# Train_Barrier.net
KiCad netlist of a schematic drawn in EasyEDA
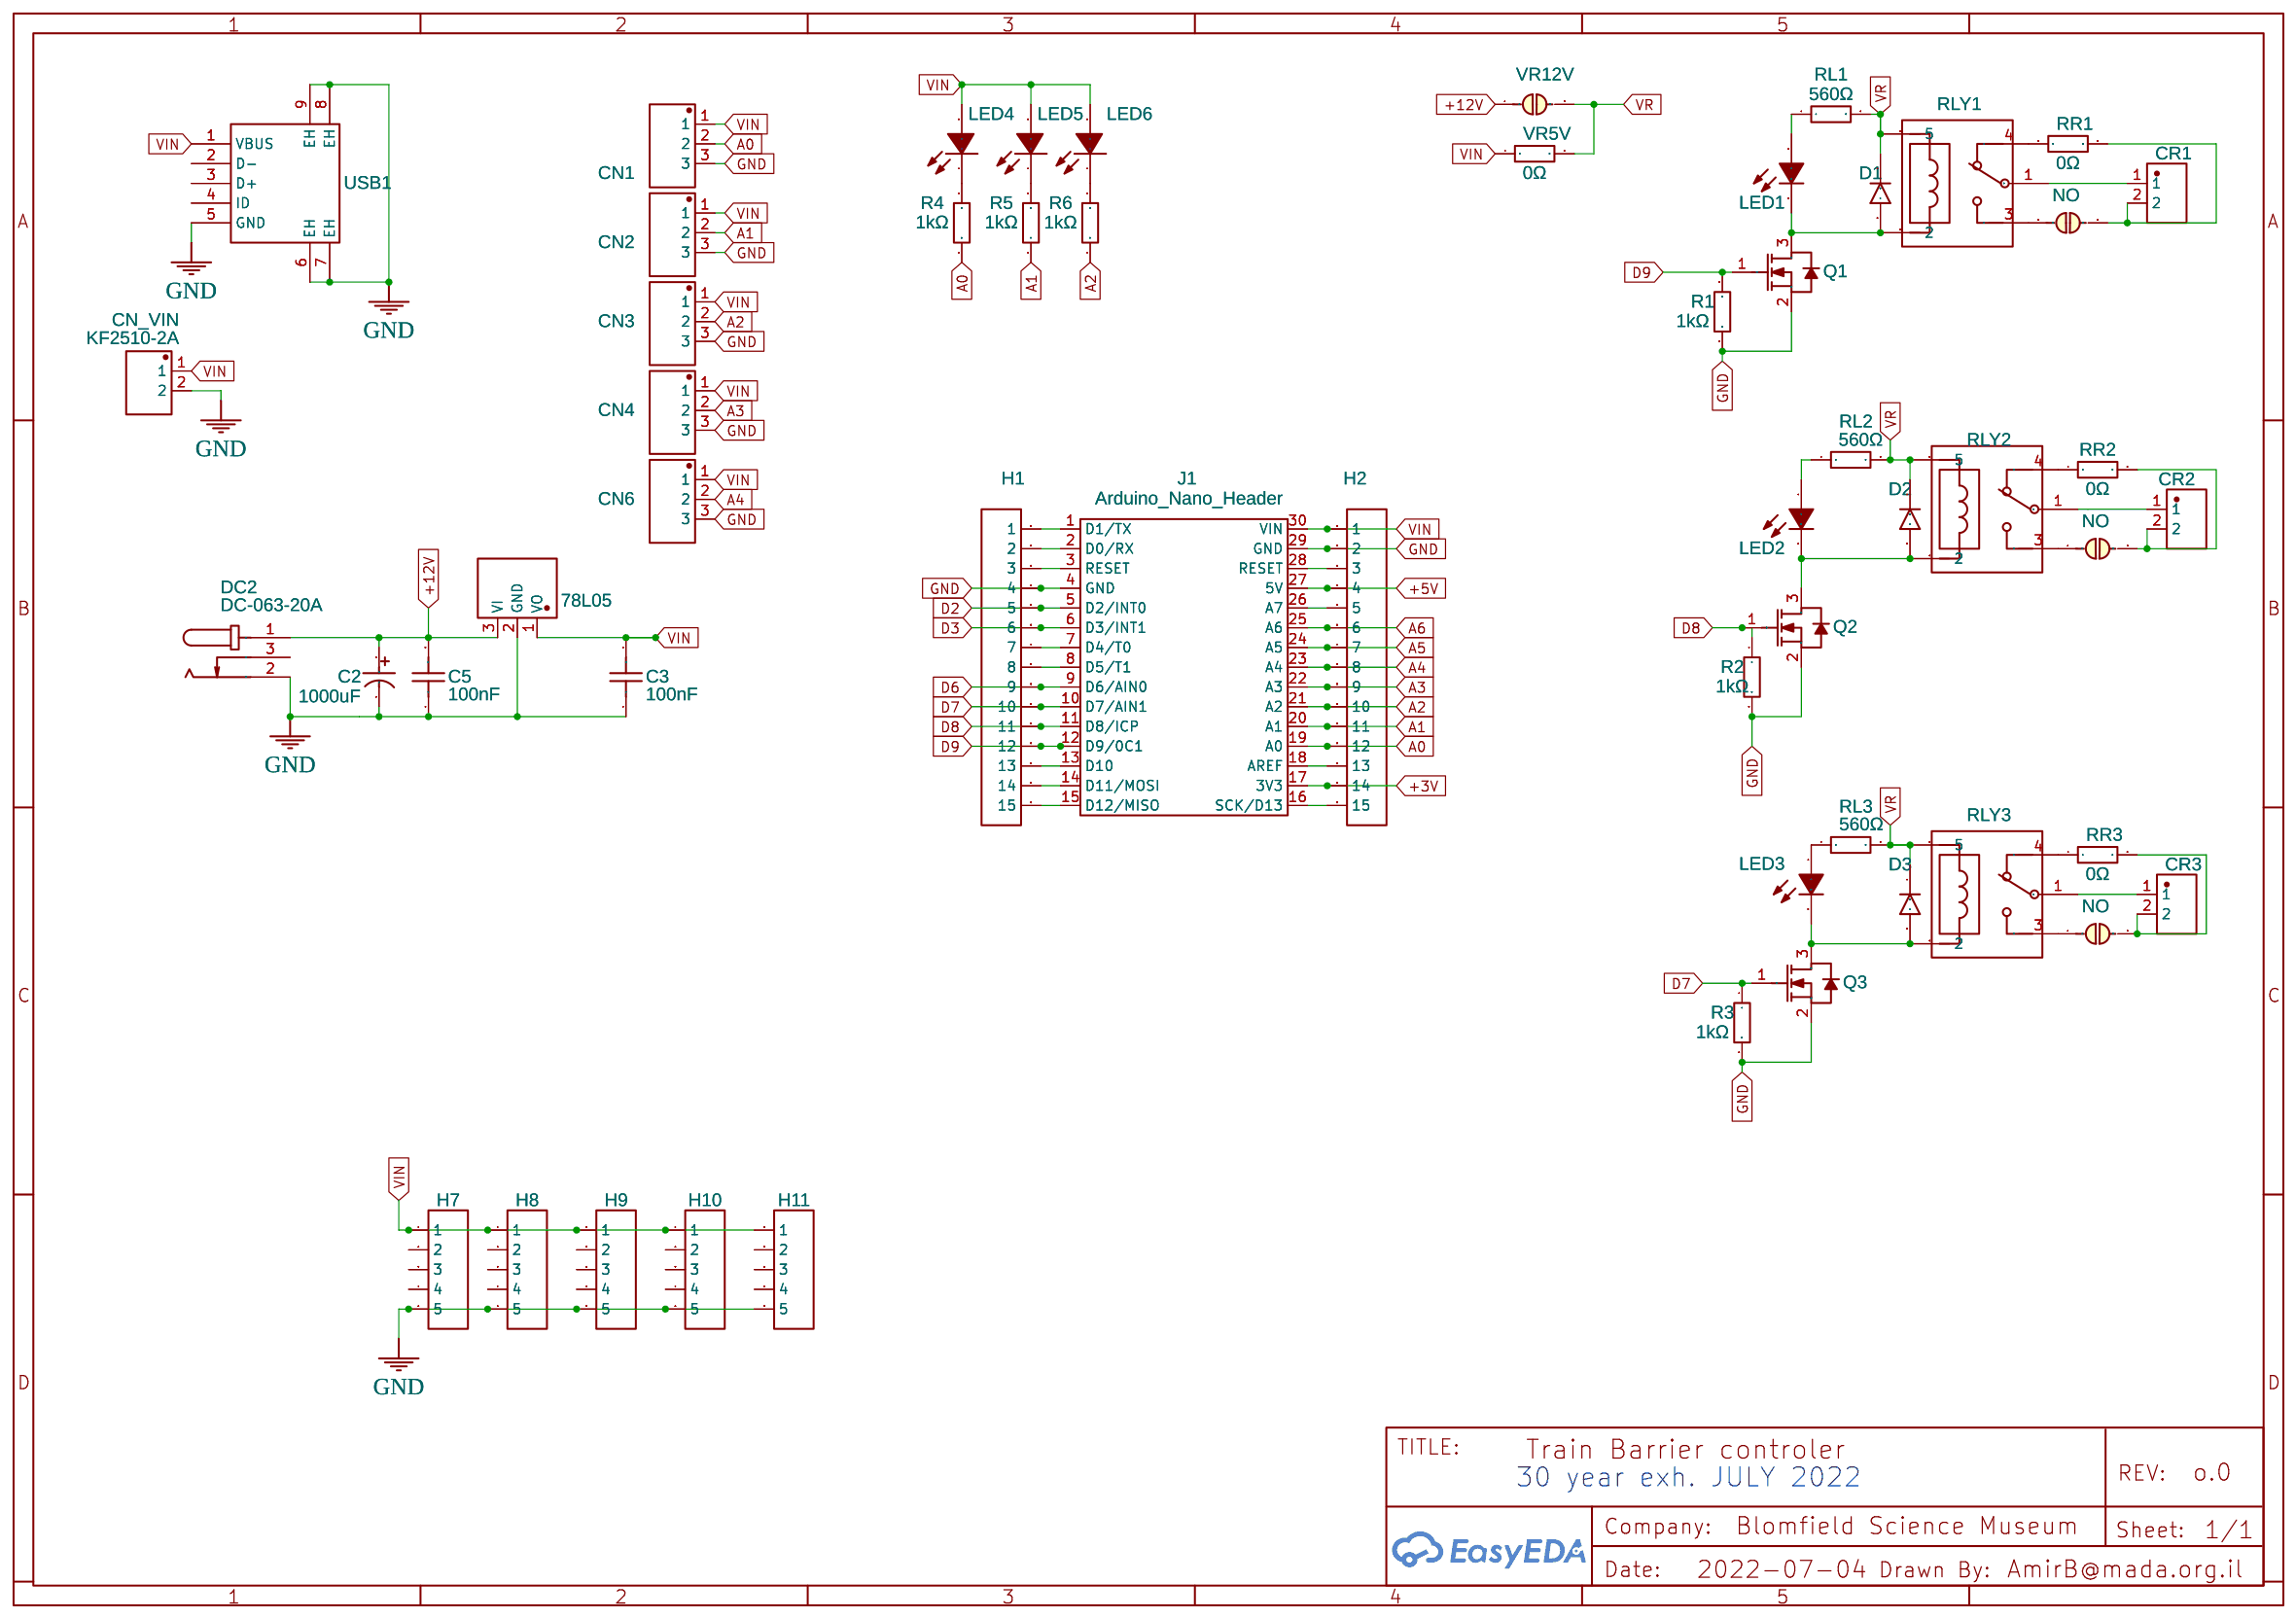
[diagram p0: schematic sheet]

(export (version "E")
  (design (tool "Eeschema 10.0.6"))
  (components
    (comp (ref "78L05")
      (value "78L05_C842819")
      (fields (field (name "BOM_Manufacturer Part") "78L05") (field (name "BOM_Supplier Part") "C842819"))
      (libsource (lib "") (part "78L05_C842819"))
    )
    (comp (ref "C2")
      (value "1000uF")
      (fields (field (name "BOM_Manufacturer Part") "1000uF 50V") (field (name "BOM_Supplier Part") "C18104"))
      (libsource (lib "") (part "1000uF 50V"))
    )
    (comp (ref "C3")
      (value "100nF")
      (fields
        (field (name "BOM_Manufacturer Part") "CC0603KRX7R9BB104")
        (field (name "BOM_Supplier Part") "C14663")
      )
      (libsource (lib "") (part "CC0603KRX7R9BB104"))
    )
    (comp (ref "C5")
      (value "100nF")
      (fields
        (field (name "BOM_Manufacturer Part") "CC0603KRX7R9BB104")
        (field (name "BOM_Supplier Part") "C14663")
      )
      (libsource (lib "") (part "CC0603KRX7R9BB104"))
    )
    (comp (ref "CN1")
      (value "KF2510-3PFlat knitting needle")
      (fields (field (name "BOM_Supplier Part") "C45011"))
      (libsource (lib "") (part "KF2510-3PFlat knitting needle"))
    )
    (comp (ref "CN2")
      (value "KF2510-3PFlat knitting needle")
      (fields (field (name "BOM_Supplier Part") "C45011"))
      (libsource (lib "") (part "KF2510-3PFlat knitting needle"))
    )
    (comp (ref "CN3")
      (value "KF2510-3PFlat knitting needle")
      (fields (field (name "BOM_Supplier Part") "C45011"))
      (libsource (lib "") (part "KF2510-3PFlat knitting needle"))
    )
    (comp (ref "CN4")
      (value "KF2510-3PFlat knitting needle")
      (fields (field (name "BOM_Supplier Part") "C45011"))
      (libsource (lib "") (part "KF2510-3PFlat knitting needle"))
    )
    (comp (ref "CN6")
      (value "KF2510-3PFlat knitting needle")
      (fields (field (name "BOM_Supplier Part") "C45011"))
      (libsource (lib "") (part "KF2510-3PFlat knitting needle"))
    )
    (comp (ref "CN_VIN")
      (value "KF2510-2A")
      (fields (field (name "BOM_Supplier Part") "C27543"))
      (libsource (lib "") (part "KF2510-2A"))
    )
    (comp (ref "CR1")
      (value "CR2")
      (fields
        (field (name "BOM_Manufacturer Part") "KF301-5.0-2P")
        (field (name "BOM_Supplier Part") "C474881")
      )
      (libsource (lib "") (part "KF301-5.0-2P"))
    )
    (comp (ref "CR2")
      (value "CR2")
      (fields
        (field (name "BOM_Manufacturer Part") "KF301-5.0-2P")
        (field (name "BOM_Supplier Part") "C474881")
      )
      (libsource (lib "") (part "KF301-5.0-2P"))
    )
    (comp (ref "CR3")
      (value "CR3")
      (fields
        (field (name "BOM_Manufacturer Part") "KF301-5.0-2P")
        (field (name "BOM_Supplier Part") "C474881")
      )
      (libsource (lib "") (part "KF301-5.0-2P"))
    )
    (comp (ref "D1")
      (value "1N4007G")
      (fields (field (name "BOM_Supplier Part") "C111122"))
      (libsource (lib "") (part "1N4007G"))
    )
    (comp (ref "D2")
      (value "1N4007G")
      (fields (field (name "BOM_Supplier Part") "C111122"))
      (libsource (lib "") (part "1N4007G"))
    )
    (comp (ref "D3")
      (value "1N4007G")
      (fields (field (name "BOM_Supplier Part") "C111122"))
      (libsource (lib "") (part "1N4007G"))
    )
    (comp (ref "DC2")
      (value "DC-063-20A")
      (fields (field (name "BOM_Supplier Part") "C707268"))
      (libsource (lib "") (part "DC-063-20A"))
    )
    (comp (ref "H1")
      (value "HDR-F-2.54_1x15")
      (fields (field (name "BOM_Supplier Part") "C124408"))
      (libsource (lib "") (part "HDR-F-2.54_1x15"))
    )
    (comp (ref "H2")
      (value "HDR-F-2.54_1x15")
      (fields (field (name "BOM_Supplier Part") "C124408"))
      (libsource (lib "") (part "HDR-F-2.54_1x15_1"))
    )
    (comp (ref "H7")
      (value "HDR-F-2.54_1x5")
      (fields (field (name "BOM_Supplier Part") "C50950"))
      (libsource (lib "") (part "HDR-F-2.54_1x5"))
    )
    (comp (ref "H8")
      (value "HDR-F-2.54_1x5")
      (fields (field (name "BOM_Supplier Part") "C50950"))
      (libsource (lib "") (part "HDR-F-2.54_1x5"))
    )
    (comp (ref "H9")
      (value "HDR-F-2.54_1x5")
      (fields (field (name "BOM_Supplier Part") "C50950"))
      (libsource (lib "") (part "HDR-F-2.54_1x5"))
    )
    (comp (ref "H10")
      (value "HDR-F-2.54_1x5")
      (fields (field (name "BOM_Supplier Part") "C50950"))
      (libsource (lib "") (part "HDR-F-2.54_1x5"))
    )
    (comp (ref "H11")
      (value "HDR-F-2.54_1x5")
      (fields (field (name "BOM_Supplier Part") "C50950"))
      (libsource (lib "") (part "HDR-F-2.54_1x5"))
    )
    (comp (ref "J1") (value "Arduino_Nano_Header") (libsource (lib "") (part "Arduino_Nano_Header")))
    (comp (ref "J1V") (value "NO") (libsource (lib "") (part "JUMPER-SMT_2_3")))
    (comp (ref "J2V") (value "NO") (libsource (lib "") (part "JUMPER-SMT_2_2")))
    (comp (ref "J3V") (value "NO") (libsource (lib "") (part "JUMPER-SMT_2_1")))
    (comp (ref "LED1")
      (value "19-217/BHC-ZL1M2RY/3T")
      (fields (field (name "BOM_Supplier Part") "C72041"))
      (libsource (lib "") (part "19-217/BHC-ZL1M2RY/3T"))
    )
    (comp (ref "LED2")
      (value "19-217/BHC-ZL1M2RY/3T")
      (fields (field (name "BOM_Supplier Part") "C72041"))
      (libsource (lib "") (part "19-217/BHC-ZL1M2RY/3T"))
    )
    (comp (ref "LED3")
      (value "19-217/BHC-ZL1M2RY/3T")
      (fields (field (name "BOM_Supplier Part") "C72041"))
      (libsource (lib "") (part "19-217/BHC-ZL1M2RY/3T"))
    )
    (comp (ref "LED4")
      (value "FC-2012HRK-620D")
      (fields (field (name "BOM_Supplier Part") "C84256"))
      (libsource (lib "") (part "FC-2012HRK-620D"))
    )
    (comp (ref "LED5")
      (value "FC-2012HRK-620D")
      (fields (field (name "BOM_Supplier Part") "C84256"))
      (libsource (lib "") (part "FC-2012HRK-620D"))
    )
    (comp (ref "LED6")
      (value "FC-2012HRK-620D")
      (fields (field (name "BOM_Supplier Part") "C84256"))
      (libsource (lib "") (part "FC-2012HRK-620D"))
    )
    (comp (ref "Q1")
      (value "AO3400_C2938367")
      (fields (field (name "BOM_Manufacturer Part") "AO3400") (field (name "BOM_Supplier Part") "C2938367"))
      (libsource (lib "") (part "AO3400_C2938367"))
    )
    (comp (ref "Q2")
      (value "AO3400_C2938367")
      (fields (field (name "BOM_Manufacturer Part") "AO3400") (field (name "BOM_Supplier Part") "C2938367"))
      (libsource (lib "") (part "AO3400_C2938367"))
    )
    (comp (ref "Q3")
      (value "AO3400_C2938367")
      (fields (field (name "BOM_Manufacturer Part") "AO3400") (field (name "BOM_Supplier Part") "C2938367"))
      (libsource (lib "") (part "AO3400_C2938367"))
    )
    (comp (ref "R1")
      (value "1kΩ")
      (fields
        (field (name "BOM_Manufacturer Part") "0603WAF1001T5E")
        (field (name "BOM_Supplier Part") "C21190")
      )
      (libsource (lib "") (part "0603WAF1001T5E_1"))
    )
    (comp (ref "R2")
      (value "1kΩ")
      (fields
        (field (name "BOM_Manufacturer Part") "0603WAF1001T5E")
        (field (name "BOM_Supplier Part") "C21190")
      )
      (libsource (lib "") (part "0603WAF1001T5E"))
    )
    (comp (ref "R3")
      (value "1kΩ")
      (fields
        (field (name "BOM_Manufacturer Part") "0603WAF1001T5E")
        (field (name "BOM_Supplier Part") "C21190")
      )
      (libsource (lib "") (part "0603WAF1001T5E"))
    )
    (comp (ref "R4")
      (value "1kΩ")
      (fields
        (field (name "BOM_Manufacturer Part") "0603WAF1001T5E")
        (field (name "BOM_Supplier Part") "C21190")
      )
      (libsource (lib "") (part "0603WAF1001T5E"))
    )
    (comp (ref "R5")
      (value "1kΩ")
      (fields
        (field (name "BOM_Manufacturer Part") "0603WAF1001T5E")
        (field (name "BOM_Supplier Part") "C21190")
      )
      (libsource (lib "") (part "0603WAF1001T5E"))
    )
    (comp (ref "R6")
      (value "1kΩ")
      (fields
        (field (name "BOM_Manufacturer Part") "0603WAF1001T5E")
        (field (name "BOM_Supplier Part") "C21190")
      )
      (libsource (lib "") (part "0603WAF1001T5E"))
    )
    (comp (ref "RL1")
      (value "560Ω")
      (fields
        (field (name "BOM_Manufacturer Part") "0603WAF5600T5E")
        (field (name "BOM_Supplier Part") "C23204")
      )
      (libsource (lib "") (part "0603WAF5600T5E"))
    )
    (comp (ref "RL2")
      (value "560Ω")
      (fields
        (field (name "BOM_Manufacturer Part") "0603WAF5600T5E")
        (field (name "BOM_Supplier Part") "C23204")
      )
      (libsource (lib "") (part "0603WAF5600T5E"))
    )
    (comp (ref "RL3")
      (value "560Ω")
      (fields
        (field (name "BOM_Manufacturer Part") "0603WAF5600T5E")
        (field (name "BOM_Supplier Part") "C23204")
      )
      (libsource (lib "") (part "0603WAF5600T5E"))
    )
    (comp (ref "RLY1")
      (value "SRA-05VDC-CL blue")
      (fields (field (name "BOM_Supplier Part") "C87714"))
      (libsource (lib "") (part "SRA-05VDC-CL blue"))
    )
    (comp (ref "RLY2")
      (value "SRA-05VDC-CL blue")
      (fields (field (name "BOM_Supplier Part") "C87714"))
      (libsource (lib "") (part "SRA-05VDC-CL blue"))
    )
    (comp (ref "RLY3")
      (value "SRA-05VDC-CL blue")
      (fields (field (name "BOM_Supplier Part") "C87714"))
      (libsource (lib "") (part "SRA-05VDC-CL blue"))
    )
    (comp (ref "RR1")
      (value "0Ω")
      (fields
        (field (name "BOM_Manufacturer Part") "0402WGF0000TCE")
        (field (name "BOM_Supplier Part") "C17168")
      )
      (libsource (lib "") (part "0402WGF0000TCE"))
    )
    (comp (ref "RR2")
      (value "0Ω")
      (fields
        (field (name "BOM_Manufacturer Part") "0402WGF0000TCE")
        (field (name "BOM_Supplier Part") "C17168")
      )
      (libsource (lib "") (part "0402WGF0000TCE"))
    )
    (comp (ref "RR3")
      (value "0Ω")
      (fields
        (field (name "BOM_Manufacturer Part") "0402WGF0000TCE")
        (field (name "BOM_Supplier Part") "C17168")
      )
      (libsource (lib "") (part "0402WGF0000TCE"))
    )
    (comp (ref "USB1")
      (value "KH-MICRO-SMT.J7.2-5P")
      (fields (field (name "BOM_Supplier Part") "C2688801"))
      (libsource (lib "") (part "KH-MICRO-SMT.J7.2-5P"))
    )
    (comp (ref "VR5V")
      (value "0Ω")
      (fields
        (field (name "BOM_Manufacturer Part") "0402WGF0000TCE")
        (field (name "BOM_Supplier Part") "C17168")
      )
      (libsource (lib "") (part "0402WGF0000TCE_1"))
    )
    (comp (ref "VR12V") (value "JUMPER-SMT_2") (libsource (lib "") (part "JUMPER-SMT_2")))
  )
  (nets
    (net (code "1") (name "+3V") (class "Default")
      (node (ref "H2") (pin "14") (pinfunction "14_14") (pintype "unspecified"))
      (node (ref "J1") (pin "17") (pinfunction "3V3_17") (pintype "unspecified"))
    )
    (net (code "2") (name "+5V") (class "Default")
      (node (ref "H2") (pin "4") (pinfunction "4_4") (pintype "unspecified"))
      (node (ref "J1") (pin "27") (pinfunction "5V_27") (pintype "unspecified"))
    )
    (net (code "3") (name "+12V") (class "Default")
      (node (ref "78L05") (pin "3") (pinfunction "VI_3") (pintype "unspecified"))
      (node (ref "C2") (pin "1") (pinfunction "1_1") (pintype "input"))
      (node (ref "C5") (pin "2") (pinfunction "2_2") (pintype "unspecified"))
      (node (ref "DC2") (pin "1") (pinfunction "1_1") (pintype "unspecified"))
      (node (ref "VR12V") (pin "1") (pinfunction "1_1") (pintype "bidirectional"))
    )
    (net (code "4") (name "A0") (class "Default")
      (node (ref "CN1") (pin "2") (pinfunction "2_2") (pintype "unspecified"))
      (node (ref "H2") (pin "12") (pinfunction "12_12") (pintype "unspecified"))
      (node (ref "J1") (pin "19") (pinfunction "A0_19") (pintype "unspecified"))
      (node (ref "R4") (pin "2") (pinfunction "2_2") (pintype "input"))
    )
    (net (code "5") (name "A1") (class "Default")
      (node (ref "CN2") (pin "2") (pinfunction "2_2") (pintype "unspecified"))
      (node (ref "H2") (pin "11") (pinfunction "11_11") (pintype "unspecified"))
      (node (ref "J1") (pin "20") (pinfunction "A1_20") (pintype "unspecified"))
      (node (ref "R5") (pin "2") (pinfunction "2_2") (pintype "input"))
    )
    (net (code "6") (name "A2") (class "Default")
      (node (ref "CN3") (pin "2") (pinfunction "2_2") (pintype "unspecified"))
      (node (ref "H2") (pin "10") (pinfunction "10_10") (pintype "unspecified"))
      (node (ref "J1") (pin "21") (pinfunction "A2_21") (pintype "unspecified"))
      (node (ref "R6") (pin "2") (pinfunction "2_2") (pintype "input"))
    )
    (net (code "7") (name "A3") (class "Default")
      (node (ref "CN4") (pin "2") (pinfunction "2_2") (pintype "unspecified"))
      (node (ref "H2") (pin "9") (pinfunction "9_9") (pintype "unspecified"))
      (node (ref "J1") (pin "22") (pinfunction "A3_22") (pintype "unspecified"))
    )
    (net (code "8") (name "A4") (class "Default")
      (node (ref "CN6") (pin "2") (pinfunction "2_2") (pintype "unspecified"))
      (node (ref "H2") (pin "8") (pinfunction "8_8") (pintype "unspecified"))
      (node (ref "J1") (pin "23") (pinfunction "A4_23") (pintype "unspecified"))
    )
    (net (code "9") (name "A5") (class "Default")
      (node (ref "H2") (pin "7") (pinfunction "7_7") (pintype "unspecified"))
      (node (ref "J1") (pin "24") (pinfunction "A5_24") (pintype "unspecified"))
    )
    (net (code "10") (name "A6") (class "Default")
      (node (ref "H2") (pin "6") (pinfunction "6_6") (pintype "unspecified"))
      (node (ref "J1") (pin "25") (pinfunction "A6_25") (pintype "unspecified"))
    )
    (net (code "11") (name "D2") (class "Default")
      (node (ref "H1") (pin "5") (pinfunction "5_5") (pintype "unspecified"))
      (node (ref "J1") (pin "5") (pinfunction "D2/INT0_5") (pintype "unspecified"))
    )
    (net (code "12") (name "D3") (class "Default")
      (node (ref "H1") (pin "6") (pinfunction "6_6") (pintype "unspecified"))
      (node (ref "J1") (pin "6") (pinfunction "D3/INT1_6") (pintype "unspecified"))
    )
    (net (code "13") (name "D6") (class "Default")
      (node (ref "H1") (pin "9") (pinfunction "9_9") (pintype "unspecified"))
      (node (ref "J1") (pin "9") (pinfunction "D6/AIN0_9") (pintype "unspecified"))
    )
    (net (code "14") (name "D7") (class "Default")
      (node (ref "H1") (pin "10") (pinfunction "10_10") (pintype "unspecified"))
      (node (ref "J1") (pin "10") (pinfunction "D7/AIN1_10") (pintype "unspecified"))
      (node (ref "Q3") (pin "1") (pinfunction "G_1") (pintype "unspecified"))
      (node (ref "R3") (pin "1") (pinfunction "1_1") (pintype "input"))
    )
    (net (code "15") (name "D8") (class "Default")
      (node (ref "H1") (pin "11") (pinfunction "11_11") (pintype "unspecified"))
      (node (ref "J1") (pin "11") (pinfunction "D8/ICP_11") (pintype "unspecified"))
      (node (ref "Q2") (pin "1") (pinfunction "G_1") (pintype "unspecified"))
      (node (ref "R2") (pin "1") (pinfunction "1_1") (pintype "input"))
    )
    (net (code "16") (name "D9") (class "Default")
      (node (ref "H1") (pin "12") (pinfunction "12_12") (pintype "unspecified"))
      (node (ref "J1") (pin "12") (pinfunction "D9/0C1_12") (pintype "unspecified"))
      (node (ref "Q1") (pin "1") (pinfunction "G_1") (pintype "unspecified"))
      (node (ref "R1") (pin "2") (pinfunction "2_2") (pintype "input"))
    )
    (net (code "17") (name "GND") (class "Default")
      (node (ref "78L05") (pin "2") (pinfunction "GND_2") (pintype "unspecified"))
      (node (ref "C2") (pin "2") (pinfunction "2_2") (pintype "input"))
      (node (ref "C3") (pin "1") (pinfunction "1_1") (pintype "unspecified"))
      (node (ref "C5") (pin "1") (pinfunction "1_1") (pintype "unspecified"))
      (node (ref "CN1") (pin "3") (pinfunction "3_3") (pintype "unspecified"))
      (node (ref "CN2") (pin "3") (pinfunction "3_3") (pintype "unspecified"))
      (node (ref "CN3") (pin "3") (pinfunction "3_3") (pintype "unspecified"))
      (node (ref "CN4") (pin "3") (pinfunction "3_3") (pintype "unspecified"))
      (node (ref "CN6") (pin "3") (pinfunction "3_3") (pintype "unspecified"))
      (node (ref "CN_VIN") (pin "2") (pinfunction "2_2") (pintype "unspecified"))
      (node (ref "DC2") (pin "2") (pinfunction "2_2") (pintype "unspecified"))
      (node (ref "H1") (pin "4") (pinfunction "4_4") (pintype "unspecified"))
      (node (ref "H10") (pin "5") (pinfunction "5_5") (pintype "unspecified"))
      (node (ref "H11") (pin "5") (pinfunction "5_5") (pintype "unspecified"))
      (node (ref "H2") (pin "2") (pinfunction "2_2") (pintype "unspecified"))
      (node (ref "H7") (pin "5") (pinfunction "5_5") (pintype "unspecified"))
      (node (ref "H8") (pin "5") (pinfunction "5_5") (pintype "unspecified"))
      (node (ref "H9") (pin "5") (pinfunction "5_5") (pintype "unspecified"))
      (node (ref "J1") (pin "29") (pinfunction "GND_29") (pintype "unspecified"))
      (node (ref "J1") (pin "4") (pinfunction "GND_4") (pintype "unspecified"))
      (node (ref "Q1") (pin "2") (pinfunction "S_2") (pintype "unspecified"))
      (node (ref "Q2") (pin "2") (pinfunction "S_2") (pintype "unspecified"))
      (node (ref "Q3") (pin "2") (pinfunction "S_2") (pintype "unspecified"))
      (node (ref "R1") (pin "1") (pinfunction "1_1") (pintype "input"))
      (node (ref "R2") (pin "2") (pinfunction "2_2") (pintype "input"))
      (node (ref "R3") (pin "2") (pinfunction "2_2") (pintype "input"))
      (node (ref "USB1") (pin "5") (pinfunction "GND_5") (pintype "unspecified"))
      (node (ref "USB1") (pin "6") (pinfunction "EH_6") (pintype "unspecified"))
      (node (ref "USB1") (pin "7") (pinfunction "EH_7") (pintype "unspecified"))
      (node (ref "USB1") (pin "8") (pinfunction "EH_8") (pintype "unspecified"))
      (node (ref "USB1") (pin "9") (pinfunction "EH_9") (pintype "unspecified"))
    )
    (net (code "18") (name "Net-(CR1-Pad1)") (class "Default")
      (node (ref "CR1") (pin "1") (pinfunction "1_1") (pintype "unspecified"))
      (node (ref "RLY1") (pin "1") (pinfunction "1_1") (pintype "unspecified"))
    )
    (net (code "19") (name "Net-(CR1-Pad2)") (class "Default")
      (node (ref "CR1") (pin "2") (pinfunction "2_2") (pintype "unspecified"))
      (node (ref "J1V") (pin "2") (pinfunction "2_2") (pintype "bidirectional"))
      (node (ref "RR1") (pin "2") (pinfunction "2_2") (pintype "input"))
    )
    (net (code "20") (name "Net-(CR2-Pad1)") (class "Default")
      (node (ref "CR2") (pin "1") (pinfunction "1_1") (pintype "unspecified"))
      (node (ref "RLY2") (pin "1") (pinfunction "1_1") (pintype "unspecified"))
    )
    (net (code "21") (name "Net-(CR2-Pad2)") (class "Default")
      (node (ref "CR2") (pin "2") (pinfunction "2_2") (pintype "unspecified"))
      (node (ref "J2V") (pin "2") (pinfunction "2_2") (pintype "bidirectional"))
      (node (ref "RR2") (pin "2") (pinfunction "2_2") (pintype "input"))
    )
    (net (code "22") (name "Net-(CR3-Pad1)") (class "Default")
      (node (ref "CR3") (pin "1") (pinfunction "1_1") (pintype "unspecified"))
      (node (ref "RLY3") (pin "1") (pinfunction "1_1") (pintype "unspecified"))
    )
    (net (code "23") (name "Net-(CR3-Pad2)") (class "Default")
      (node (ref "CR3") (pin "2") (pinfunction "2_2") (pintype "unspecified"))
      (node (ref "J3V") (pin "2") (pinfunction "2_2") (pintype "bidirectional"))
      (node (ref "RR3") (pin "2") (pinfunction "2_2") (pintype "input"))
    )
    (net (code "24") (name "Net-(D1-A)") (class "Default")
      (node (ref "D1") (pin "2") (pinfunction "A_2") (pintype "unspecified"))
      (node (ref "LED1") (pin "2") (pinfunction "C_2") (pintype "input"))
      (node (ref "Q1") (pin "3") (pinfunction "D_3") (pintype "unspecified"))
      (node (ref "RLY1") (pin "2") (pinfunction "2_2") (pintype "unspecified"))
    )
    (net (code "25") (name "Net-(D2-A)") (class "Default")
      (node (ref "D2") (pin "2") (pinfunction "A_2") (pintype "unspecified"))
      (node (ref "LED2") (pin "2") (pinfunction "C_2") (pintype "input"))
      (node (ref "Q2") (pin "3") (pinfunction "D_3") (pintype "unspecified"))
      (node (ref "RLY2") (pin "2") (pinfunction "2_2") (pintype "unspecified"))
    )
    (net (code "26") (name "Net-(D3-A)") (class "Default")
      (node (ref "D3") (pin "2") (pinfunction "A_2") (pintype "unspecified"))
      (node (ref "LED3") (pin "2") (pinfunction "C_2") (pintype "input"))
      (node (ref "Q3") (pin "3") (pinfunction "D_3") (pintype "unspecified"))
      (node (ref "RLY3") (pin "2") (pinfunction "2_2") (pintype "unspecified"))
    )
    (net (code "27") (name "Net-(H1-Pad3)") (class "Default")
      (node (ref "H1") (pin "3") (pinfunction "3_3") (pintype "unspecified"))
      (node (ref "J1") (pin "3") (pinfunction "RESET_3") (pintype "unspecified"))
    )
    (net (code "28") (name "Net-(H2-Pad3)") (class "Default")
      (node (ref "H2") (pin "3") (pinfunction "3_3") (pintype "unspecified"))
      (node (ref "J1") (pin "28") (pinfunction "RESET_28") (pintype "unspecified"))
    )
    (net (code "29") (name "Net-(J1-A7)") (class "Default")
      (node (ref "H2") (pin "5") (pinfunction "5_5") (pintype "unspecified"))
      (node (ref "J1") (pin "26") (pinfunction "A7_26") (pintype "unspecified"))
    )
    (net (code "30") (name "Net-(J1-AREF)") (class "Default")
      (node (ref "H2") (pin "13") (pinfunction "13_13") (pintype "unspecified"))
      (node (ref "J1") (pin "18") (pinfunction "AREF_18") (pintype "unspecified"))
    )
    (net (code "31") (name "Net-(J1-D0{slash}RX)") (class "Default")
      (node (ref "H1") (pin "2") (pinfunction "2_2") (pintype "unspecified"))
      (node (ref "J1") (pin "2") (pinfunction "D0/RX_2") (pintype "unspecified"))
    )
    (net (code "32") (name "Net-(J1-D1{slash}TX)") (class "Default")
      (node (ref "H1") (pin "1") (pinfunction "1_1") (pintype "unspecified"))
      (node (ref "J1") (pin "1") (pinfunction "D1/TX_1") (pintype "unspecified"))
    )
    (net (code "33") (name "Net-(J1-D4{slash}T0)") (class "Default")
      (node (ref "H1") (pin "7") (pinfunction "7_7") (pintype "unspecified"))
      (node (ref "J1") (pin "7") (pinfunction "D4/T0_7") (pintype "unspecified"))
    )
    (net (code "34") (name "Net-(J1-D5{slash}T1)") (class "Default")
      (node (ref "H1") (pin "8") (pinfunction "8_8") (pintype "unspecified"))
      (node (ref "J1") (pin "8") (pinfunction "D5/T1_8") (pintype "unspecified"))
    )
    (net (code "35") (name "Net-(J1-D10)") (class "Default")
      (node (ref "H1") (pin "13") (pinfunction "13_13") (pintype "unspecified"))
      (node (ref "J1") (pin "13") (pinfunction "D10_13") (pintype "unspecified"))
    )
    (net (code "36") (name "Net-(J1-D11{slash}MOSI)") (class "Default")
      (node (ref "H1") (pin "14") (pinfunction "14_14") (pintype "unspecified"))
      (node (ref "J1") (pin "14") (pinfunction "D11/MOSI_14") (pintype "unspecified"))
    )
    (net (code "37") (name "Net-(J1-D12{slash}MISO)") (class "Default")
      (node (ref "H1") (pin "15") (pinfunction "15_15") (pintype "unspecified"))
      (node (ref "J1") (pin "15") (pinfunction "D12/MISO_15") (pintype "unspecified"))
    )
    (net (code "38") (name "Net-(J1-SCK{slash}D13)") (class "Default")
      (node (ref "H2") (pin "15") (pinfunction "15_15") (pintype "unspecified"))
      (node (ref "J1") (pin "16") (pinfunction "SCK/D13_16") (pintype "unspecified"))
    )
    (net (code "39") (name "Net-(J1V-Pad1)") (class "Default")
      (node (ref "J1V") (pin "1") (pinfunction "1_1") (pintype "bidirectional"))
      (node (ref "RLY1") (pin "3") (pinfunction "3_3") (pintype "unspecified"))
    )
    (net (code "40") (name "Net-(J2V-Pad1)") (class "Default")
      (node (ref "J2V") (pin "1") (pinfunction "1_1") (pintype "bidirectional"))
      (node (ref "RLY2") (pin "3") (pinfunction "3_3") (pintype "unspecified"))
    )
    (net (code "41") (name "Net-(J3V-Pad1)") (class "Default")
      (node (ref "J3V") (pin "1") (pinfunction "1_1") (pintype "bidirectional"))
      (node (ref "RLY3") (pin "3") (pinfunction "3_3") (pintype "unspecified"))
    )
    (net (code "42") (name "Net-(LED1-A)") (class "Default")
      (node (ref "LED1") (pin "1") (pinfunction "A_1") (pintype "input"))
      (node (ref "RL1") (pin "1") (pinfunction "1_1") (pintype "input"))
    )
    (net (code "43") (name "Net-(LED2-A)") (class "Default")
      (node (ref "LED2") (pin "1") (pinfunction "A_1") (pintype "input"))
      (node (ref "RL2") (pin "1") (pinfunction "1_1") (pintype "input"))
    )
    (net (code "44") (name "Net-(LED3-A)") (class "Default")
      (node (ref "LED3") (pin "1") (pinfunction "A_1") (pintype "input"))
      (node (ref "RL3") (pin "1") (pinfunction "1_1") (pintype "input"))
    )
    (net (code "45") (name "Net-(LED4--)") (class "Default")
      (node (ref "LED4") (pin "1") (pinfunction "-_1") (pintype "unspecified"))
      (node (ref "R4") (pin "1") (pinfunction "1_1") (pintype "input"))
    )
    (net (code "46") (name "Net-(LED5--)") (class "Default")
      (node (ref "LED5") (pin "1") (pinfunction "-_1") (pintype "unspecified"))
      (node (ref "R5") (pin "1") (pinfunction "1_1") (pintype "input"))
    )
    (net (code "47") (name "Net-(LED6--)") (class "Default")
      (node (ref "LED6") (pin "1") (pinfunction "-_1") (pintype "unspecified"))
      (node (ref "R6") (pin "1") (pinfunction "1_1") (pintype "input"))
    )
    (net (code "48") (name "Net-(RLY1-Pad4)") (class "Default")
      (node (ref "RLY1") (pin "4") (pinfunction "4_4") (pintype "unspecified"))
      (node (ref "RR1") (pin "1") (pinfunction "1_1") (pintype "input"))
    )
    (net (code "49") (name "Net-(RLY2-Pad4)") (class "Default")
      (node (ref "RLY2") (pin "4") (pinfunction "4_4") (pintype "unspecified"))
      (node (ref "RR2") (pin "1") (pinfunction "1_1") (pintype "input"))
    )
    (net (code "50") (name "Net-(RLY3-Pad4)") (class "Default")
      (node (ref "RLY3") (pin "4") (pinfunction "4_4") (pintype "unspecified"))
      (node (ref "RR3") (pin "1") (pinfunction "1_1") (pintype "input"))
    )
    (net (code "51") (name "VIN") (class "Default")
      (node (ref "78L05") (pin "1") (pinfunction "VO_1") (pintype "unspecified"))
      (node (ref "C3") (pin "2") (pinfunction "2_2") (pintype "unspecified"))
      (node (ref "CN1") (pin "1") (pinfunction "1_1") (pintype "unspecified"))
      (node (ref "CN2") (pin "1") (pinfunction "1_1") (pintype "unspecified"))
      (node (ref "CN3") (pin "1") (pinfunction "1_1") (pintype "unspecified"))
      (node (ref "CN4") (pin "1") (pinfunction "1_1") (pintype "unspecified"))
      (node (ref "CN6") (pin "1") (pinfunction "1_1") (pintype "unspecified"))
      (node (ref "CN_VIN") (pin "1") (pinfunction "1_1") (pintype "unspecified"))
      (node (ref "H10") (pin "1") (pinfunction "1_1") (pintype "unspecified"))
      (node (ref "H11") (pin "1") (pinfunction "1_1") (pintype "unspecified"))
      (node (ref "H2") (pin "1") (pinfunction "1_1") (pintype "unspecified"))
      (node (ref "H7") (pin "1") (pinfunction "1_1") (pintype "unspecified"))
      (node (ref "H8") (pin "1") (pinfunction "1_1") (pintype "unspecified"))
      (node (ref "H9") (pin "1") (pinfunction "1_1") (pintype "unspecified"))
      (node (ref "J1") (pin "30") (pinfunction "VIN_30") (pintype "unspecified"))
      (node (ref "LED4") (pin "2") (pinfunction "+_2") (pintype "unspecified"))
      (node (ref "LED5") (pin "2") (pinfunction "+_2") (pintype "unspecified"))
      (node (ref "LED6") (pin "2") (pinfunction "+_2") (pintype "unspecified"))
      (node (ref "USB1") (pin "1") (pinfunction "VBUS_1") (pintype "unspecified"))
      (node (ref "VR5V") (pin "1") (pinfunction "1_1") (pintype "input"))
    )
    (net (code "52") (name "VR") (class "Default")
      (node (ref "D1") (pin "1") (pinfunction "C_1") (pintype "unspecified"))
      (node (ref "D2") (pin "1") (pinfunction "C_1") (pintype "unspecified"))
      (node (ref "D3") (pin "1") (pinfunction "C_1") (pintype "unspecified"))
      (node (ref "RL1") (pin "2") (pinfunction "2_2") (pintype "input"))
      (node (ref "RL2") (pin "2") (pinfunction "2_2") (pintype "input"))
      (node (ref "RL3") (pin "2") (pinfunction "2_2") (pintype "input"))
      (node (ref "RLY1") (pin "5") (pinfunction "5_5") (pintype "unspecified"))
      (node (ref "RLY2") (pin "5") (pinfunction "5_5") (pintype "unspecified"))
      (node (ref "RLY3") (pin "5") (pinfunction "5_5") (pintype "unspecified"))
      (node (ref "VR12V") (pin "2") (pinfunction "2_2") (pintype "bidirectional"))
      (node (ref "VR5V") (pin "2") (pinfunction "2_2") (pintype "input"))
    )
    (net (code "53") (name "unconnected-(DC2-Pad3)") (class "Default")
      (node (ref "DC2") (pin "3") (pinfunction "3_3") (pintype "unspecified"))
    )
    (net (code "54") (name "unconnected-(H7-Pad2)") (class "Default")
      (node (ref "H7") (pin "2") (pinfunction "2_2") (pintype "unspecified"))
    )
    (net (code "55") (name "unconnected-(H7-Pad3)") (class "Default")
      (node (ref "H7") (pin "3") (pinfunction "3_3") (pintype "unspecified"))
    )
    (net (code "56") (name "unconnected-(H7-Pad4)") (class "Default")
      (node (ref "H7") (pin "4") (pinfunction "4_4") (pintype "unspecified"))
    )
    (net (code "57") (name "unconnected-(H8-Pad2)") (class "Default")
      (node (ref "H8") (pin "2") (pinfunction "2_2") (pintype "unspecified"))
    )
    (net (code "58") (name "unconnected-(H8-Pad3)") (class "Default")
      (node (ref "H8") (pin "3") (pinfunction "3_3") (pintype "unspecified"))
    )
    (net (code "59") (name "unconnected-(H8-Pad4)") (class "Default")
      (node (ref "H8") (pin "4") (pinfunction "4_4") (pintype "unspecified"))
    )
    (net (code "60") (name "unconnected-(H9-Pad2)") (class "Default")
      (node (ref "H9") (pin "2") (pinfunction "2_2") (pintype "unspecified"))
    )
    (net (code "61") (name "unconnected-(H9-Pad3)") (class "Default")
      (node (ref "H9") (pin "3") (pinfunction "3_3") (pintype "unspecified"))
    )
    (net (code "62") (name "unconnected-(H9-Pad4)") (class "Default")
      (node (ref "H9") (pin "4") (pinfunction "4_4") (pintype "unspecified"))
    )
    (net (code "63") (name "unconnected-(H10-Pad2)") (class "Default")
      (node (ref "H10") (pin "2") (pinfunction "2_2") (pintype "unspecified"))
    )
    (net (code "64") (name "unconnected-(H10-Pad3)") (class "Default")
      (node (ref "H10") (pin "3") (pinfunction "3_3") (pintype "unspecified"))
    )
    (net (code "65") (name "unconnected-(H10-Pad4)") (class "Default")
      (node (ref "H10") (pin "4") (pinfunction "4_4") (pintype "unspecified"))
    )
    (net (code "66") (name "unconnected-(H11-Pad2)") (class "Default")
      (node (ref "H11") (pin "2") (pinfunction "2_2") (pintype "unspecified"))
    )
    (net (code "67") (name "unconnected-(H11-Pad3)") (class "Default")
      (node (ref "H11") (pin "3") (pinfunction "3_3") (pintype "unspecified"))
    )
    (net (code "68") (name "unconnected-(H11-Pad4)") (class "Default")
      (node (ref "H11") (pin "4") (pinfunction "4_4") (pintype "unspecified"))
    )
    (net (code "69") (name "unconnected-(USB1-D+-Pad3)") (class "Default")
      (node (ref "USB1") (pin "3") (pinfunction "D+_3") (pintype "unspecified"))
    )
    (net (code "70") (name "unconnected-(USB1-D--Pad2)") (class "Default")
      (node (ref "USB1") (pin "2") (pinfunction "D-_2") (pintype "unspecified"))
    )
    (net (code "71") (name "unconnected-(USB1-ID-Pad4)") (class "Default")
      (node (ref "USB1") (pin "4") (pinfunction "ID_4") (pintype "unspecified"))
    )
  )
)
